# 3__ENC28J60.net
KiCad netlist of a schematic drawn in Altium Designer
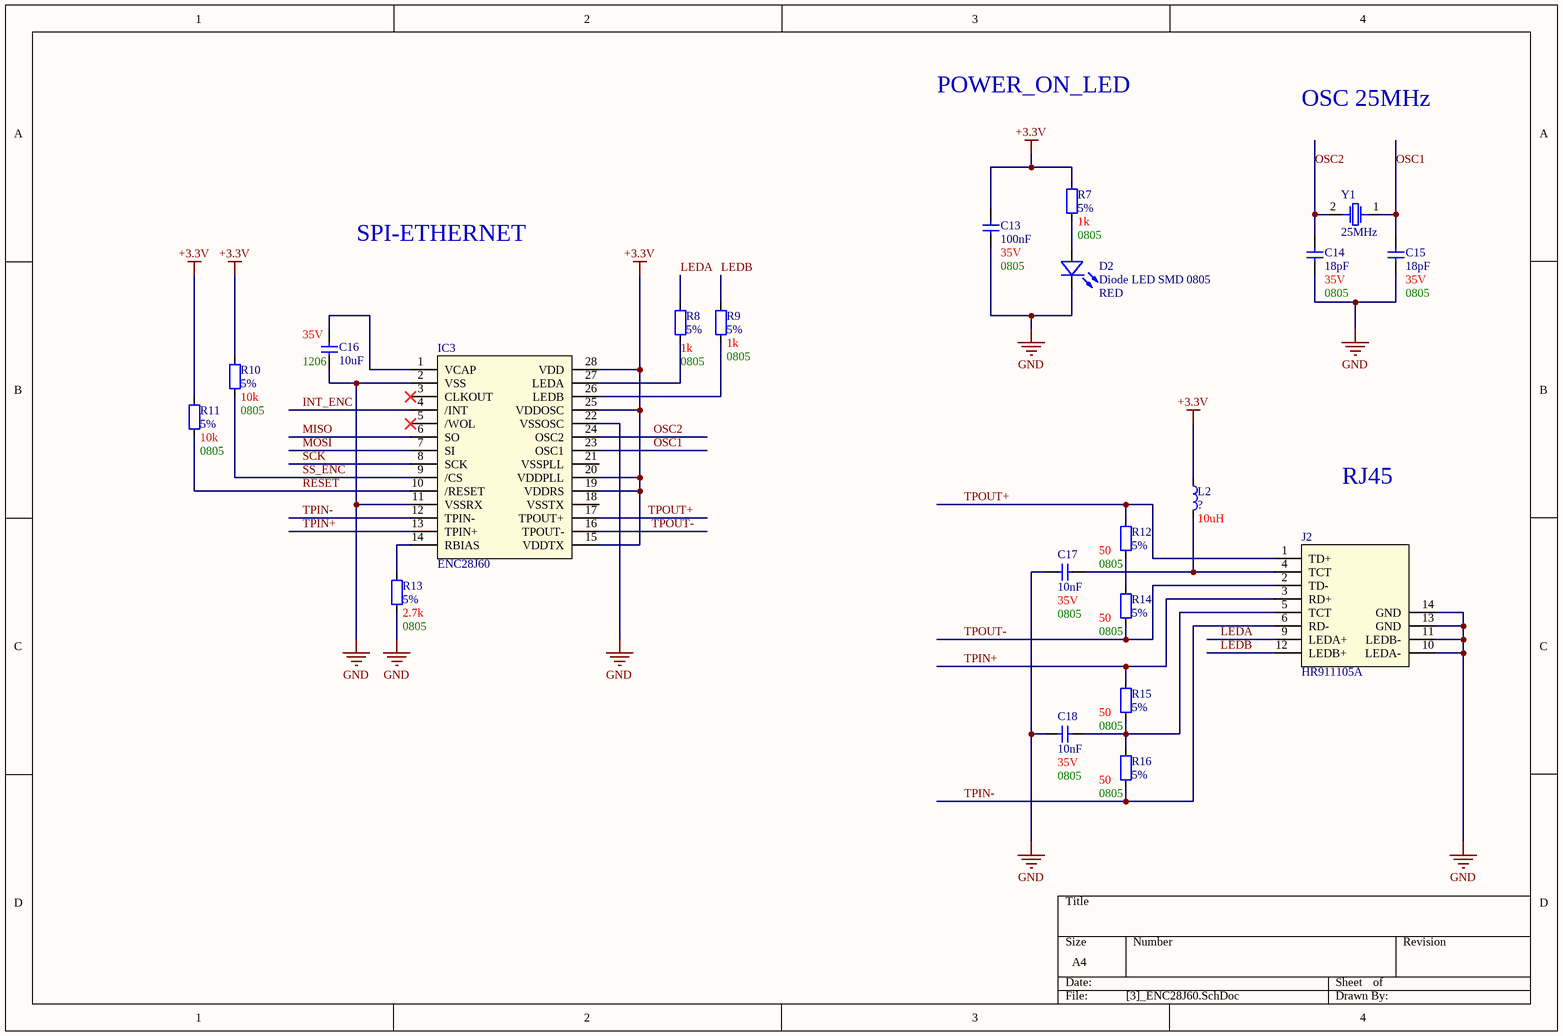
[diagram p0: [3]_ENC28J60.SchDoc]

(export (version "E")
  (design (tool "Eeschema 10.0.6"))
  (components
    (comp (ref "C13")
      (value "100nF")
      (footprint "Capacitor_0805")
      (description "Ceramic Capacitor SMD 0805")
      (fields
        (field (name "TOLERANCE") "10%")
        (field (name "VOLTAGE") "35V")
        (field (name "PACKAGE") "0805")
        (field (name "Comment") "Capacitor SMD 0805")
      )
      (libsource (lib "AKN_PI_Library") (part "Capacitor SMD 0805"))
    )
    (comp (ref "C14")
      (value "18pF")
      (footprint "Capacitor_0805")
      (description "Ceramic Capacitor SMD 0805")
      (fields
        (field (name "TOLERANCE") "10%")
        (field (name "VOLTAGE") "35V")
        (field (name "PACKAGE") "0805")
        (field (name "Comment") "Capacitor SMD 0805")
      )
      (libsource (lib "AKN_PI_Library") (part "Capacitor SMD 0805"))
    )
    (comp (ref "C15")
      (value "18pF")
      (footprint "Capacitor_0805")
      (description "Ceramic Capacitor SMD 0805")
      (fields
        (field (name "TOLERANCE") "10%")
        (field (name "VOLTAGE") "35V")
        (field (name "PACKAGE") "0805")
        (field (name "Comment") "Capacitor SMD 0805")
      )
      (libsource (lib "AKN_PI_Library") (part "Capacitor SMD 0805"))
    )
    (comp (ref "C16")
      (value "10uF")
      (footprint "CAP_SMD_1206")
      (description "Ceramic Capacitor SMD 1206")
      (fields
        (field (name "TOLERANCE") "10%")
        (field (name "VOLTAGE") "35V")
        (field (name "PACKAGE") "1206")
        (field (name "Comment") "Capacitor SMD 1206")
      )
      (libsource (lib "AKN_PI_Library") (part "Capacitor SMD 1206"))
    )
    (comp (ref "C17")
      (value "10nF")
      (footprint "Capacitor_0805")
      (description "Ceramic Capacitor SMD 0805")
      (fields
        (field (name "TOLERANCE") "10%")
        (field (name "VOLTAGE") "35V")
        (field (name "PACKAGE") "0805")
        (field (name "Comment") "Capacitor SMD 0805")
      )
      (libsource (lib "AKN_PI_Library") (part "Capacitor SMD 0805"))
    )
    (comp (ref "C18")
      (value "10nF")
      (footprint "Capacitor_0805")
      (description "Ceramic Capacitor SMD 0805")
      (fields
        (field (name "TOLERANCE") "10%")
        (field (name "VOLTAGE") "35V")
        (field (name "PACKAGE") "0805")
        (field (name "Comment") "Capacitor SMD 0805")
      )
      (libsource (lib "AKN_PI_Library") (part "Capacitor SMD 0805"))
    )
    (comp (ref "D2")
      (value "Diode LED SMD 0805")
      (footprint "Diode_LED_SMD_0805")
      (fields (field (name "COLOUR") "RED"))
      (libsource (lib "AKN_PI_Library") (part "Diode LED SMD 0805"))
    )
    (comp (ref "IC3")
      (value "ENC28J60")
      (footprint "SO-28W")
      (description "ENC28J60 - Stand-Alone Ethernet Controller  with SPI Interface")
      (libsource (lib "AKN_PI_Library") (part "ENC28J60"))
    )
    (comp (ref "J2")
      (value "HR911105A")
      (footprint "HR911105A")
      (description "HR911105A - Ethernet connector RJ45")
      (libsource (lib "AKN_PI_Library") (part "HR911105A"))
    )
    (comp (ref "L2")
      (value "?")
      (footprint "IND_IHLP2525")
      (description "Power Inductor IHLP2525 Series")
      (fields (field (name "ALTIUM_VALUE") "10uH"))
      (libsource (lib "AKN_PI_Library") (part "IHLP2525CZER150M01"))
    )
    (comp (ref "R7")
      (value "1k")
      (footprint "R_0805")
      (description "Resistor SMD 0805")
      (fields (field (name "TOLERANCE") "5%") (field (name "PACKAGE") "0805"))
      (libsource (lib "AKN_PI_Library") (part "Resistor SMD 0805"))
    )
    (comp (ref "R8")
      (value "1k")
      (footprint "R_0805")
      (description "Resistor SMD 0805")
      (fields (field (name "TOLERANCE") "5%") (field (name "PACKAGE") "0805"))
      (libsource (lib "AKN_PI_Library") (part "Resistor SMD 0805"))
    )
    (comp (ref "R9")
      (value "1k")
      (footprint "R_0805")
      (description "Resistor SMD 0805")
      (fields (field (name "TOLERANCE") "5%") (field (name "PACKAGE") "0805"))
      (libsource (lib "AKN_PI_Library") (part "Resistor SMD 0805"))
    )
    (comp (ref "R10")
      (value "10k")
      (footprint "R_0805")
      (description "Resistor SMD 0805")
      (fields (field (name "TOLERANCE") "5%") (field (name "PACKAGE") "0805"))
      (libsource (lib "AKN_PI_Library") (part "Resistor SMD 0805"))
    )
    (comp (ref "R11")
      (value "10k")
      (footprint "R_0805")
      (description "Resistor SMD 0805")
      (fields (field (name "TOLERANCE") "5%") (field (name "PACKAGE") "0805"))
      (libsource (lib "") (part "Resistor SMD 0805_1"))
    )
    (comp (ref "R12")
      (value "50")
      (footprint "R_0805")
      (description "Resistor SMD 0805")
      (fields (field (name "TOLERANCE") "5%") (field (name "PACKAGE") "0805"))
      (libsource (lib "AKN_PI_Library") (part "Resistor SMD 0805"))
    )
    (comp (ref "R13")
      (value "2.7k")
      (footprint "R_0805")
      (description "Resistor SMD 0805")
      (fields (field (name "TOLERANCE") "5%") (field (name "PACKAGE") "0805"))
      (libsource (lib "AKN_PI_Library") (part "Resistor SMD 0805"))
    )
    (comp (ref "R14")
      (value "50")
      (footprint "R_0805")
      (description "Resistor SMD 0805")
      (fields (field (name "TOLERANCE") "5%") (field (name "PACKAGE") "0805"))
      (libsource (lib "AKN_PI_Library") (part "Resistor SMD 0805"))
    )
    (comp (ref "R15")
      (value "50")
      (footprint "R_0805")
      (description "Resistor SMD 0805")
      (fields (field (name "TOLERANCE") "5%") (field (name "PACKAGE") "0805"))
      (libsource (lib "AKN_PI_Library") (part "Resistor SMD 0805"))
    )
    (comp (ref "R16")
      (value "50")
      (footprint "R_0805")
      (description "Resistor SMD 0805")
      (fields (field (name "TOLERANCE") "5%") (field (name "PACKAGE") "0805"))
      (libsource (lib "AKN_PI_Library") (part "Resistor SMD 0805"))
    )
    (comp (ref "Y1")
      (value "25MHz")
      (footprint "HC49SM")
      (description "HC49SM - Crystal oscilator")
      (fields (field (name "Comment") "HC49SM"))
      (libsource (lib "AKN_PI_Library") (part "HC49SM"))
    )
  )
  (nets
    (net (code "1") (name "+3.3V") (class "Default")
      (node (ref "C13") (pin "2") (pinfunction "2_2") (pintype "passive"))
      (node (ref "IC3") (pin "15") (pinfunction "VDDTX_15") (pintype "passive"))
      (node (ref "IC3") (pin "19") (pinfunction "VDDRS_19") (pintype "passive"))
      (node (ref "IC3") (pin "20") (pinfunction "VDDPLL_20") (pintype "passive"))
      (node (ref "IC3") (pin "25") (pinfunction "VDDOSC_25") (pintype "passive"))
      (node (ref "IC3") (pin "28") (pinfunction "VDD_28") (pintype "passive"))
      (node (ref "L2") (pin "1") (pinfunction "1_1") (pintype "passive"))
      (node (ref "R10") (pin "2") (pinfunction "2_2") (pintype "passive"))
      (node (ref "R11") (pin "1") (pinfunction "1_1") (pintype "passive"))
      (node (ref "R7") (pin "2") (pinfunction "2_2") (pintype "passive"))
    )
    (net (code "2") (name "/INT_ENC") (class "Default")
      (node (ref "IC3") (pin "4") (pinfunction "/INT_4") (pintype "passive"))
    )
    (net (code "3") (name "/LEDA") (class "Default")
      (node (ref "J2") (pin "9") (pinfunction "LEDA+_9") (pintype "passive"))
      (node (ref "R8") (pin "2") (pinfunction "2_2") (pintype "passive"))
    )
    (net (code "4") (name "/LEDB") (class "Default")
      (node (ref "J2") (pin "12") (pinfunction "LEDB+_12") (pintype "passive"))
      (node (ref "R9") (pin "2") (pinfunction "2_2") (pintype "passive"))
    )
    (net (code "5") (name "/MISO") (class "Default")
      (node (ref "IC3") (pin "6") (pinfunction "SO_6") (pintype "passive"))
    )
    (net (code "6") (name "/MOSI") (class "Default")
      (node (ref "IC3") (pin "7") (pinfunction "SI_7") (pintype "passive"))
    )
    (net (code "8") (name "/OSC1") (class "Default")
      (node (ref "C15") (pin "1") (pinfunction "1_1") (pintype "passive"))
      (node (ref "IC3") (pin "23") (pinfunction "OSC1_23") (pintype "passive"))
      (node (ref "Y1") (pin "1") (pinfunction "1_1") (pintype "passive"))
    )
    (net (code "9") (name "/OSC2") (class "Default")
      (node (ref "C14") (pin "1") (pinfunction "1_1") (pintype "passive"))
      (node (ref "IC3") (pin "24") (pinfunction "OSC2_24") (pintype "passive"))
      (node (ref "Y1") (pin "2") (pinfunction "2_2") (pintype "passive"))
    )
    (net (code "11") (name "/RESET") (class "Default")
      (node (ref "IC3") (pin "10") (pinfunction "/RESET_10") (pintype "passive"))
      (node (ref "R11") (pin "2") (pinfunction "2_2") (pintype "passive"))
    )
    (net (code "13") (name "/SCK") (class "Default")
      (node (ref "IC3") (pin "8") (pinfunction "SCK_8") (pintype "passive"))
    )
    (net (code "15") (name "/SS_ENC") (class "Default")
      (node (ref "IC3") (pin "9") (pinfunction "/CS_9") (pintype "passive"))
      (node (ref "R10") (pin "1") (pinfunction "1_1") (pintype "passive"))
    )
    (net (code "16") (name "/TPIN+") (class "Default")
      (node (ref "IC3") (pin "13") (pinfunction "TPIN+_13") (pintype "passive"))
      (node (ref "J2") (pin "3") (pinfunction "RD+_3") (pintype "passive"))
      (node (ref "R15") (pin "2") (pinfunction "2_2") (pintype "passive"))
    )
    (net (code "17") (name "/TPIN-") (class "Default")
      (node (ref "IC3") (pin "12") (pinfunction "TPIN-_12") (pintype "passive"))
      (node (ref "J2") (pin "6") (pinfunction "RD-_6") (pintype "passive"))
      (node (ref "R16") (pin "1") (pinfunction "1_1") (pintype "passive"))
    )
    (net (code "18") (name "/TPOUT+") (class "Default")
      (node (ref "IC3") (pin "17") (pinfunction "TPOUT+_17") (pintype "passive"))
      (node (ref "J2") (pin "1") (pinfunction "TD+_1") (pintype "passive"))
      (node (ref "R12") (pin "2") (pinfunction "2_2") (pintype "passive"))
    )
    (net (code "19") (name "/TPOUT-") (class "Default")
      (node (ref "IC3") (pin "16") (pinfunction "TPOUT-_16") (pintype "passive"))
      (node (ref "J2") (pin "2") (pinfunction "TD-_2") (pintype "passive"))
      (node (ref "R14") (pin "1") (pinfunction "1_1") (pintype "passive"))
    )
    (net (code "20") (name "GND") (class "Default")
      (node (ref "C13") (pin "1") (pinfunction "1_1") (pintype "passive"))
      (node (ref "C14") (pin "2") (pinfunction "2_2") (pintype "passive"))
      (node (ref "C15") (pin "2") (pinfunction "2_2") (pintype "passive"))
      (node (ref "C16") (pin "1") (pinfunction "1_1") (pintype "passive"))
      (node (ref "C17") (pin "1") (pinfunction "1_1") (pintype "passive"))
      (node (ref "C18") (pin "1") (pinfunction "1_1") (pintype "passive"))
      (node (ref "D2") (pin "C") (pinfunction "C_C") (pintype "passive"))
      (node (ref "IC3") (pin "11") (pinfunction "VSSRX_11") (pintype "passive"))
      (node (ref "IC3") (pin "2") (pinfunction "VSS_2") (pintype "passive"))
      (node (ref "IC3") (pin "22") (pinfunction "VSSOSC_22") (pintype "passive"))
      (node (ref "J2") (pin "10") (pinfunction "LEDA-_10") (pintype "passive"))
      (node (ref "J2") (pin "11") (pinfunction "LEDB-_11") (pintype "passive"))
      (node (ref "J2") (pin "13") (pinfunction "GND_13") (pintype "passive"))
      (node (ref "J2") (pin "14") (pinfunction "GND_14") (pintype "passive"))
      (node (ref "R13") (pin "1") (pinfunction "1_1") (pintype "passive"))
    )
    (net (code "21") (name "Net-(C17-Pad2)") (class "Default")
      (node (ref "C17") (pin "2") (pinfunction "2_2") (pintype "passive"))
      (node (ref "J2") (pin "4") (pinfunction "TCT_4") (pintype "passive"))
      (node (ref "L2") (pin "2") (pinfunction "2_2") (pintype "passive"))
    )
    (net (code "22") (name "Net-(C18-Pad2)") (class "Default")
      (node (ref "C18") (pin "2") (pinfunction "2_2") (pintype "passive"))
      (node (ref "J2") (pin "5") (pinfunction "TCT_5") (pintype "passive"))
      (node (ref "R15") (pin "1") (pinfunction "1_1") (pintype "passive"))
      (node (ref "R16") (pin "2") (pinfunction "2_2") (pintype "passive"))
    )
    (net (code "23") (name "Net-(D2-PadA)") (class "Default")
      (node (ref "D2") (pin "A") (pinfunction "A_A") (pintype "passive"))
      (node (ref "R7") (pin "1") (pinfunction "1_1") (pintype "passive"))
    )
    (net (code "24") (name "Net-(IC3-LEDA)") (class "Default")
      (node (ref "IC3") (pin "27") (pinfunction "LEDA_27") (pintype "passive"))
      (node (ref "R8") (pin "1") (pinfunction "1_1") (pintype "passive"))
    )
    (net (code "25") (name "Net-(IC3-LEDB)") (class "Default")
      (node (ref "IC3") (pin "26") (pinfunction "LEDB_26") (pintype "passive"))
      (node (ref "R9") (pin "1") (pinfunction "1_1") (pintype "passive"))
    )
    (net (code "26") (name "Net-(IC3-RBIAS)") (class "Default")
      (node (ref "IC3") (pin "14") (pinfunction "RBIAS_14") (pintype "passive"))
      (node (ref "R13") (pin "2") (pinfunction "2_2") (pintype "passive"))
    )
    (net (code "27") (name "Net-(IC3-VCAP)") (class "Default")
      (node (ref "C16") (pin "2") (pinfunction "2_2") (pintype "passive"))
      (node (ref "IC3") (pin "1") (pinfunction "VCAP_1") (pintype "passive"))
    )
    (net (code "28") (name "Net-(R12-Pad1)") (class "Default")
      (node (ref "R12") (pin "1") (pinfunction "1_1") (pintype "passive"))
      (node (ref "R14") (pin "2") (pinfunction "2_2") (pintype "passive"))
    )
    (net (code "29") (name "unconnected-(IC3-CLKOUT-Pad3)") (class "Default")
      (node (ref "IC3") (pin "3") (pinfunction "CLKOUT_3") (pintype "passive+no_connect"))
    )
    (net (code "30") (name "unconnected-(IC3-VSSPLL-Pad21)") (class "Default")
      (node (ref "IC3") (pin "21") (pinfunction "VSSPLL_21") (pintype "passive"))
    )
    (net (code "31") (name "unconnected-(IC3-VSSTX-Pad18)") (class "Default")
      (node (ref "IC3") (pin "18") (pinfunction "VSSTX_18") (pintype "passive"))
    )
    (net (code "32") (name "unconnected-(IC3-{slash}WOL-Pad5)") (class "Default")
      (node (ref "IC3") (pin "5") (pinfunction "/WOL_5") (pintype "passive+no_connect"))
    )
  )
)
